# pi_zero_shield.net
KiCad netlist of a schematic drawn in EAGLE
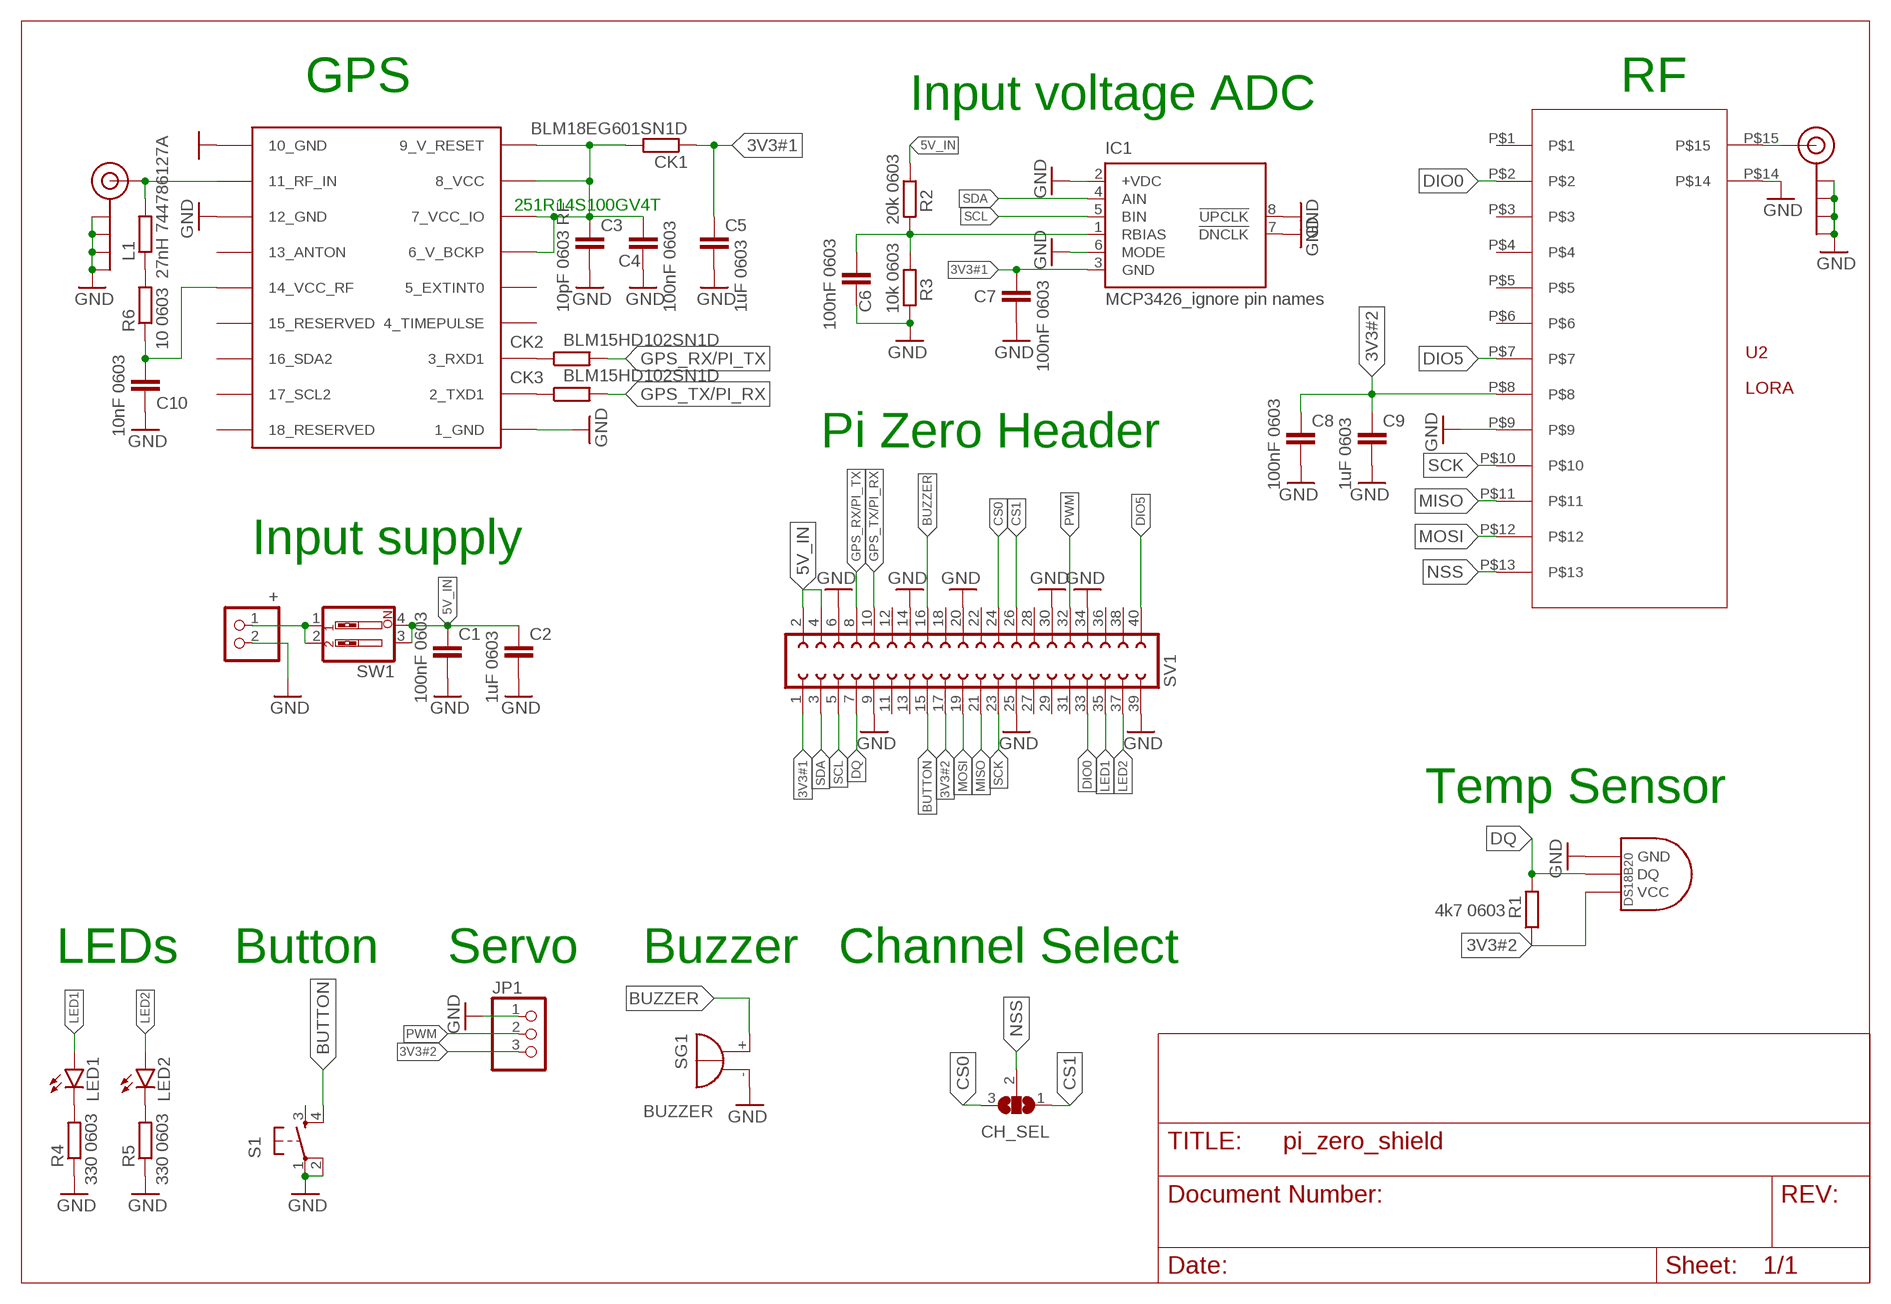
[diagram p0: schematic, sheet 1]

(export (version "E")
  (design (tool "Eeschema 10.0.6"))
  (components
    (comp (ref "+")
      (value "PINHD-1X2")
      (footprint "eagle-import:1X02")
      (libsource (lib "eagle-import") (part "PINHD-1X2"))
    )
    (comp (ref "C1")
      (value "100nF 0603")
      (footprint "eagle-import:C0603K")
      (libsource (lib "eagle-import") (part "C-EUC0603K"))
    )
    (comp (ref "C2")
      (value "1uF 0603")
      (footprint "eagle-import:C0603K")
      (libsource (lib "eagle-import") (part "C-EUC0603K"))
    )
    (comp (ref "C3")
      (value "10pF 0603 RF")
      (footprint "eagle-import:C0603K")
      (libsource (lib "eagle-import") (part "C-EUC0603K"))
    )
    (comp (ref "C4")
      (value "100nF 0603")
      (footprint "eagle-import:C0603K")
      (libsource (lib "eagle-import") (part "C-EUC0603K"))
    )
    (comp (ref "C5")
      (value "1uF 0603")
      (footprint "eagle-import:C0603K")
      (libsource (lib "eagle-import") (part "C-EUC0603K"))
    )
    (comp (ref "C6")
      (value "100nF 0603")
      (footprint "eagle-import:C0603K")
      (libsource (lib "eagle-import") (part "C-EUC0603K"))
    )
    (comp (ref "C7")
      (value "100nF 0603")
      (footprint "eagle-import:C0603K")
      (libsource (lib "eagle-import") (part "C-EUC0603K"))
    )
    (comp (ref "C8")
      (value "100nF 0603")
      (footprint "eagle-import:C0603K")
      (libsource (lib "eagle-import") (part "C-EUC0603K"))
    )
    (comp (ref "C9")
      (value "1uF 0603")
      (footprint "eagle-import:C0603K")
      (libsource (lib "eagle-import") (part "C-EUC0603K"))
    )
    (comp (ref "C10")
      (value "10nF 0603")
      (footprint "eagle-import:C0603K")
      (libsource (lib "eagle-import") (part "C-EUC0603K"))
    )
    (comp (ref "CH_SEL")
      (value "SJ2W")
      (footprint "eagle-import:SJ_2")
      (libsource (lib "eagle-import") (part "SJ2W"))
    )
    (comp (ref "CK1")
      (value "BLM18EG601SN1D")
      (footprint "eagle-import:R0603")
      (libsource (lib "eagle-import") (part "R-EU_R0603"))
    )
    (comp (ref "CK2")
      (value "BLM15HD102SN1D")
      (footprint "eagle-import:R0402")
      (libsource (lib "eagle-import") (part "R-EU_R0402"))
    )
    (comp (ref "CK3")
      (value "BLM15HD102SN1D")
      (footprint "eagle-import:R0402")
      (libsource (lib "eagle-import") (part "R-EU_R0402"))
    )
    (comp (ref "IC1")
      (value "MCP3426_ignore pin names")
      (footprint "eagle-import:SOIC08")
      (libsource (lib "eagle-import") (part "LS7183-SOIC"))
    )
    (comp (ref "J$2")
      (value "SMA_EDGE")
      (footprint "eagle-import:SMA-EDGE")
      (libsource (lib "eagle-import") (part "SMA_EDGE"))
    )
    (comp (ref "JP1")
      (value "PINHD-1X3")
      (footprint "eagle-import:1X03")
      (libsource (lib "eagle-import") (part "PINHD-1X3"))
    )
    (comp (ref "L1")
      (value "27nH 744786127A")
      (footprint "eagle-import:R0603")
      (libsource (lib "eagle-import") (part "R-EU_R0603"))
    )
    (comp (ref "LED1")
      (value "LEDSML0603")
      (footprint "eagle-import:SML0603")
      (libsource (lib "eagle-import") (part "LEDSML0603"))
    )
    (comp (ref "LED2")
      (value "LEDSML0603")
      (footprint "eagle-import:SML0603")
      (libsource (lib "eagle-import") (part "LEDSML0603"))
    )
    (comp (ref "R1")
      (value "4k7 0603")
      (footprint "eagle-import:R0603")
      (libsource (lib "eagle-import") (part "R-EU_R0603"))
    )
    (comp (ref "R2")
      (value "20k 0603")
      (footprint "eagle-import:R0603")
      (libsource (lib "eagle-import") (part "R-EU_R0603"))
    )
    (comp (ref "R3")
      (value "10k 0603")
      (footprint "eagle-import:R0603")
      (libsource (lib "eagle-import") (part "R-EU_R0603"))
    )
    (comp (ref "R4")
      (value "330 0603")
      (footprint "eagle-import:R0603")
      (libsource (lib "eagle-import") (part "R-EU_R0603"))
    )
    (comp (ref "R5")
      (value "330 0603")
      (footprint "eagle-import:R0603")
      (libsource (lib "eagle-import") (part "R-EU_R0603"))
    )
    (comp (ref "R6")
      (value "10 0603")
      (footprint "eagle-import:R0603")
      (libsource (lib "eagle-import") (part "R-EU_R0603"))
    )
    (comp (ref "S1")
      (value "DTS-6")
      (footprint "eagle-import:DTS-6")
      (libsource (lib "eagle-import") (part "DTS-6"))
    )
    (comp (ref "SG1")
      (value "BUZZER")
      (footprint "eagle-import:BMT1205XH7.5")
      (libsource (lib "eagle-import") (part "BMT1205XH7.5"))
    )
    (comp (ref "SV1")
      (value "FE20-2")
      (footprint "eagle-import:FE20-2")
      (libsource (lib "eagle-import") (part "FE20-2"))
    )
    (comp (ref "SW1")
      (value "SW_DIP-2")
      (footprint "eagle-import:EDG-02")
      (libsource (lib "eagle-import") (part "SW_DIP-2"))
    )
    (comp (ref "U$1")
      (value "TAOGLAS.AP.10X.01")
      (footprint "eagle-import:TAOGLAS.AP.10X.01")
      (fields (field (name "SPICEPREFIX") "X"))
      (libsource (lib "eagle-import") (part "TAOGLAS.AP.10X.01"))
    )
    (comp (ref "U$4")
      (value "DS1820SOIC")
      (footprint "eagle-import:DS18B20_SOIC")
      (libsource (lib "eagle-import") (part "DS1820SOIC"))
    )
    (comp (ref "U1")
      (value "U1")
      (footprint "eagle-import:UBLOX_MAX-6")
      (libsource (lib "eagle-import") (part "UBLOX_MAX-6"))
    )
    (comp (ref "U2")
      (value "LORA")
      (footprint "eagle-import:LORA_DRF")
      (libsource (lib "eagle-import") (part "LORA"))
    )
  )
  (nets
    (net (code "1") (name "3V3#1") (class "Default")
      (node (ref "C5") (pin "1") (pinfunction "1_1") (pintype "passive"))
      (node (ref "C7") (pin "1") (pinfunction "1_1") (pintype "passive"))
      (node (ref "CK1") (pin "1") (pinfunction "1_1") (pintype "passive"))
      (node (ref "IC1") (pin "3") (pinfunction "GND_3") (pintype "power_in"))
      (node (ref "SV1") (pin "1") (pinfunction "1_1") (pintype "passive"))
    )
    (net (code "2") (name "3V3#2") (class "Default")
      (node (ref "C8") (pin "1") (pinfunction "1_1") (pintype "passive"))
      (node (ref "C9") (pin "1") (pinfunction "1_1") (pintype "passive"))
      (node (ref "JP1") (pin "3") (pinfunction "3_3") (pintype "passive"))
      (node (ref "R1") (pin "1") (pinfunction "1_1") (pintype "passive"))
      (node (ref "SV1") (pin "17") (pinfunction "17_17") (pintype "passive"))
      (node (ref "U$4") (pin "VCC") (pinfunction "VCC_VCC") (pintype "power_in"))
      (node (ref "U2") (pin "P$8") (pinfunction "P$8_P$8") (pintype "bidirectional"))
    )
    (net (code "3") (name "5V_IN") (class "Default")
      (node (ref "C1") (pin "1") (pinfunction "1_1") (pintype "passive"))
      (node (ref "C2") (pin "1") (pinfunction "1_1") (pintype "passive"))
      (node (ref "R2") (pin "1") (pinfunction "1_1") (pintype "passive"))
      (node (ref "SV1") (pin "2") (pinfunction "2_2") (pintype "passive"))
      (node (ref "SV1") (pin "4") (pinfunction "4_4") (pintype "passive"))
      (node (ref "SW1") (pin "3") (pinfunction "3_3") (pintype "passive"))
      (node (ref "SW1") (pin "4") (pinfunction "4_4") (pintype "passive"))
    )
    (net (code "4") (name "BUTTON") (class "Default")
      (node (ref "S1") (pin "4") (pinfunction "4_4") (pintype "passive"))
      (node (ref "SV1") (pin "15") (pinfunction "15_15") (pintype "passive"))
    )
    (net (code "5") (name "BUZZER") (class "Default")
      (node (ref "SG1") (pin "+") (pinfunction "+_+") (pintype "passive"))
      (node (ref "SV1") (pin "16") (pinfunction "16_16") (pintype "passive"))
    )
    (net (code "6") (name "CS0") (class "Default")
      (node (ref "CH_SEL") (pin "3") (pinfunction "3_3") (pintype "passive"))
      (node (ref "SV1") (pin "24") (pinfunction "24_24") (pintype "passive"))
    )
    (net (code "7") (name "CS1") (class "Default")
      (node (ref "CH_SEL") (pin "1") (pinfunction "1_1") (pintype "passive"))
      (node (ref "SV1") (pin "26") (pinfunction "26_26") (pintype "passive"))
    )
    (net (code "8") (name "DIO0") (class "Default")
      (node (ref "SV1") (pin "33") (pinfunction "33_33") (pintype "passive"))
      (node (ref "U2") (pin "P$2") (pinfunction "P$2_P$2") (pintype "bidirectional"))
    )
    (net (code "9") (name "DIO5") (class "Default")
      (node (ref "SV1") (pin "40") (pinfunction "40_40") (pintype "passive"))
      (node (ref "U2") (pin "P$7") (pinfunction "P$7_P$7") (pintype "bidirectional"))
    )
    (net (code "10") (name "DQ") (class "Default")
      (node (ref "R1") (pin "2") (pinfunction "2_2") (pintype "passive"))
      (node (ref "SV1") (pin "7") (pinfunction "7_7") (pintype "passive"))
      (node (ref "U$4") (pin "DQ") (pinfunction "DQ_DQ") (pintype "bidirectional"))
    )
    (net (code "11") (name "GND") (class "Default")
      (node (ref "+") (pin "2") (pinfunction "2_2") (pintype "passive"))
      (node (ref "C1") (pin "2") (pinfunction "2_2") (pintype "passive"))
      (node (ref "C10") (pin "2") (pinfunction "2_2") (pintype "passive"))
      (node (ref "C2") (pin "2") (pinfunction "2_2") (pintype "passive"))
      (node (ref "C3") (pin "2") (pinfunction "2_2") (pintype "passive"))
      (node (ref "C4") (pin "2") (pinfunction "2_2") (pintype "passive"))
      (node (ref "C5") (pin "2") (pinfunction "2_2") (pintype "passive"))
      (node (ref "C6") (pin "2") (pinfunction "2_2") (pintype "passive"))
      (node (ref "C7") (pin "2") (pinfunction "2_2") (pintype "passive"))
      (node (ref "C8") (pin "2") (pinfunction "2_2") (pintype "passive"))
      (node (ref "C9") (pin "2") (pinfunction "2_2") (pintype "passive"))
      (node (ref "IC1") (pin "2") (pinfunction "+VDC_2") (pintype "input"))
      (node (ref "IC1") (pin "6") (pinfunction "MODE_6") (pintype "input"))
      (node (ref "IC1") (pin "7") (pinfunction "~{DNCLK}_7") (pintype "input"))
      (node (ref "IC1") (pin "8") (pinfunction "~{UPCLK}_8") (pintype "input"))
      (node (ref "J$2") (pin "GND@0") (pinfunction "GND_GND@0") (pintype "bidirectional"))
      (node (ref "J$2") (pin "GND@1") (pinfunction "GND_GND@1") (pintype "bidirectional"))
      (node (ref "J$2") (pin "GND@2") (pinfunction "GND_GND@2") (pintype "bidirectional"))
      (node (ref "J$2") (pin "GND@3") (pinfunction "GND_GND@3") (pintype "bidirectional"))
      (node (ref "JP1") (pin "1") (pinfunction "1_1") (pintype "passive"))
      (node (ref "R3") (pin "2") (pinfunction "2_2") (pintype "passive"))
      (node (ref "R4") (pin "1") (pinfunction "1_1") (pintype "passive"))
      (node (ref "R5") (pin "1") (pinfunction "1_1") (pintype "passive"))
      (node (ref "S1") (pin "1") (pinfunction "1_1") (pintype "passive"))
      (node (ref "S1") (pin "2") (pinfunction "2_2") (pintype "passive"))
      (node (ref "SG1") (pin "-") (pinfunction "-_-") (pintype "passive"))
      (node (ref "SV1") (pin "14") (pinfunction "14_14") (pintype "passive"))
      (node (ref "SV1") (pin "20") (pinfunction "20_20") (pintype "passive"))
      (node (ref "SV1") (pin "25") (pinfunction "25_25") (pintype "passive"))
      (node (ref "SV1") (pin "30") (pinfunction "30_30") (pintype "passive"))
      (node (ref "SV1") (pin "34") (pinfunction "34_34") (pintype "passive"))
      (node (ref "SV1") (pin "39") (pinfunction "39_39") (pintype "passive"))
      (node (ref "SV1") (pin "6") (pinfunction "6_6") (pintype "passive"))
      (node (ref "SV1") (pin "9") (pinfunction "9_9") (pintype "passive"))
      (node (ref "U$1") (pin "GP$1") (pinfunction "GND_GP$1") (pintype "bidirectional"))
      (node (ref "U$1") (pin "GP$2") (pinfunction "GND_GP$2") (pintype "bidirectional"))
      (node (ref "U$1") (pin "GP$3") (pinfunction "GND_GP$3") (pintype "bidirectional"))
      (node (ref "U$1") (pin "GP$4") (pinfunction "GND_GP$4") (pintype "bidirectional"))
      (node (ref "U$4") (pin "GND") (pinfunction "GND_GND") (pintype "power_in"))
      (node (ref "U1") (pin "10_GND") (pinfunction "10_GND_10_GND") (pintype "power_in"))
      (node (ref "U1") (pin "12_GND") (pinfunction "12_GND_12_GND") (pintype "power_in"))
      (node (ref "U1") (pin "1_GND") (pinfunction "1_GND_1_GND") (pintype "power_in"))
      (node (ref "U2") (pin "P$14") (pinfunction "P$14_P$14") (pintype "bidirectional"))
      (node (ref "U2") (pin "P$9") (pinfunction "P$9_P$9") (pintype "bidirectional"))
    )
    (net (code "12") (name "GPS_RX{slash}PI_TX") (class "Default")
      (node (ref "CK2") (pin "2") (pinfunction "2_2") (pintype "passive"))
      (node (ref "SV1") (pin "8") (pinfunction "8_8") (pintype "passive"))
    )
    (net (code "13") (name "GPS_TX{slash}PI_RX") (class "Default")
      (node (ref "CK3") (pin "2") (pinfunction "2_2") (pintype "passive"))
      (node (ref "SV1") (pin "10") (pinfunction "10_10") (pintype "passive"))
    )
    (net (code "14") (name "LED1") (class "Default")
      (node (ref "LED1") (pin "A") (pinfunction "A_A") (pintype "passive"))
      (node (ref "SV1") (pin "35") (pinfunction "35_35") (pintype "passive"))
    )
    (net (code "15") (name "LED2") (class "Default")
      (node (ref "LED2") (pin "A") (pinfunction "A_A") (pintype "passive"))
      (node (ref "SV1") (pin "37") (pinfunction "37_37") (pintype "passive"))
    )
    (net (code "16") (name "MISO") (class "Default")
      (node (ref "SV1") (pin "21") (pinfunction "21_21") (pintype "passive"))
      (node (ref "U2") (pin "P$11") (pinfunction "P$11_P$11") (pintype "bidirectional"))
    )
    (net (code "17") (name "MOSI") (class "Default")
      (node (ref "SV1") (pin "19") (pinfunction "19_19") (pintype "passive"))
      (node (ref "U2") (pin "P$12") (pinfunction "P$12_P$12") (pintype "bidirectional"))
    )
    (net (code "18") (name "NSS") (class "Default")
      (node (ref "CH_SEL") (pin "2") (pinfunction "2_2") (pintype "passive"))
      (node (ref "U2") (pin "P$13") (pinfunction "P$13_P$13") (pintype "bidirectional"))
    )
    (net (code "19") (name "Net-(+-Pad1)") (class "Default")
      (node (ref "+") (pin "1") (pinfunction "1_1") (pintype "passive"))
      (node (ref "SW1") (pin "1") (pinfunction "1_1") (pintype "passive"))
      (node (ref "SW1") (pin "2") (pinfunction "2_2") (pintype "passive"))
    )
    (net (code "20") (name "Net-(C3-Pad1)") (class "Default")
      (node (ref "C3") (pin "1") (pinfunction "1_1") (pintype "passive"))
      (node (ref "C4") (pin "1") (pinfunction "1_1") (pintype "passive"))
      (node (ref "CK1") (pin "2") (pinfunction "2_2") (pintype "passive"))
      (node (ref "U1") (pin "6_V_BCKP") (pinfunction "6_V_BCKP_6_V_BCKP") (pintype "bidirectional"))
      (node (ref "U1") (pin "7_VCC_IO") (pinfunction "7_VCC_IO_7_VCC_IO") (pintype "power_in"))
      (node (ref "U1") (pin "8_VCC") (pinfunction "8_VCC_8_VCC") (pintype "power_in"))
      (node (ref "U1") (pin "9_V_RESET") (pinfunction "9_V_RESET_9_V_RESET") (pintype "power_in"))
    )
    (net (code "21") (name "Net-(C10-Pad1)") (class "Default")
      (node (ref "C10") (pin "1") (pinfunction "1_1") (pintype "passive"))
      (node (ref "R6") (pin "1") (pinfunction "1_1") (pintype "passive"))
      (node (ref "U1") (pin "14_VCC_RF") (pinfunction "14_VCC_RF_14_VCC_RF") (pintype "bidirectional"))
    )
    (net (code "22") (name "Net-(CK2-Pad1)") (class "Default")
      (node (ref "CK2") (pin "1") (pinfunction "1_1") (pintype "passive"))
      (node (ref "U1") (pin "3_RXD1") (pinfunction "3_RXD1_3_RXD1") (pintype "bidirectional"))
    )
    (net (code "23") (name "Net-(CK3-Pad1)") (class "Default")
      (node (ref "CK3") (pin "1") (pinfunction "1_1") (pintype "passive"))
      (node (ref "U1") (pin "2_TXD1") (pinfunction "2_TXD1_2_TXD1") (pintype "bidirectional"))
    )
    (net (code "24") (name "Net-(IC1-RBIAS)") (class "Default")
      (node (ref "C6") (pin "1") (pinfunction "1_1") (pintype "passive"))
      (node (ref "IC1") (pin "1") (pinfunction "RBIAS_1") (pintype "input"))
      (node (ref "R2") (pin "2") (pinfunction "2_2") (pintype "passive"))
      (node (ref "R3") (pin "1") (pinfunction "1_1") (pintype "passive"))
    )
    (net (code "25") (name "Net-(J$2-SIGNAL)") (class "Default")
      (node (ref "J$2") (pin "SIG") (pinfunction "SIGNAL_SIG") (pintype "bidirectional"))
      (node (ref "U2") (pin "P$15") (pinfunction "P$15_P$15") (pintype "bidirectional"))
    )
    (net (code "26") (name "Net-(L1-Pad1)") (class "Default")
      (node (ref "L1") (pin "1") (pinfunction "1_1") (pintype "passive"))
      (node (ref "R6") (pin "2") (pinfunction "2_2") (pintype "passive"))
    )
    (net (code "27") (name "Net-(L1-Pad2)") (class "Default")
      (node (ref "L1") (pin "2") (pinfunction "2_2") (pintype "passive"))
      (node (ref "U$1") (pin "FP$1") (pinfunction "SIGNAL_FP$1") (pintype "bidirectional"))
      (node (ref "U$1") (pin "FP$2") (pinfunction "SIGNAL_FP$2") (pintype "bidirectional"))
      (node (ref "U1") (pin "11_RF_IN") (pinfunction "11_RF_IN_11_RF_IN") (pintype "bidirectional"))
    )
    (net (code "28") (name "Net-(LED1-PadC)") (class "Default")
      (node (ref "LED1") (pin "C") (pinfunction "C_C") (pintype "passive"))
      (node (ref "R4") (pin "2") (pinfunction "2_2") (pintype "passive"))
    )
    (net (code "29") (name "Net-(LED2-PadC)") (class "Default")
      (node (ref "LED2") (pin "C") (pinfunction "C_C") (pintype "passive"))
      (node (ref "R5") (pin "2") (pinfunction "2_2") (pintype "passive"))
    )
    (net (code "30") (name "PWM") (class "Default")
      (node (ref "JP1") (pin "2") (pinfunction "2_2") (pintype "passive"))
      (node (ref "SV1") (pin "32") (pinfunction "32_32") (pintype "passive"))
    )
    (net (code "31") (name "SCK") (class "Default")
      (node (ref "SV1") (pin "23") (pinfunction "23_23") (pintype "passive"))
      (node (ref "U2") (pin "P$10") (pinfunction "P$10_P$10") (pintype "bidirectional"))
    )
    (net (code "32") (name "SCL") (class "Default")
      (node (ref "IC1") (pin "5") (pinfunction "BIN_5") (pintype "input"))
      (node (ref "SV1") (pin "5") (pinfunction "5_5") (pintype "passive"))
    )
    (net (code "33") (name "SDA") (class "Default")
      (node (ref "IC1") (pin "4") (pinfunction "AIN_4") (pintype "input"))
      (node (ref "SV1") (pin "3") (pinfunction "3_3") (pintype "passive"))
    )
    (net (code "34") (name "unconnected-(S1-Pad3)") (class "Default")
      (node (ref "S1") (pin "3") (pinfunction "3_3") (pintype "passive"))
    )
    (net (code "35") (name "unconnected-(SV1-Pad11)") (class "Default")
      (node (ref "SV1") (pin "11") (pinfunction "11_11") (pintype "passive"))
    )
    (net (code "36") (name "unconnected-(SV1-Pad12)") (class "Default")
      (node (ref "SV1") (pin "12") (pinfunction "12_12") (pintype "passive"))
    )
    (net (code "37") (name "unconnected-(SV1-Pad13)") (class "Default")
      (node (ref "SV1") (pin "13") (pinfunction "13_13") (pintype "passive"))
    )
    (net (code "38") (name "unconnected-(SV1-Pad18)") (class "Default")
      (node (ref "SV1") (pin "18") (pinfunction "18_18") (pintype "passive"))
    )
    (net (code "39") (name "unconnected-(SV1-Pad22)") (class "Default")
      (node (ref "SV1") (pin "22") (pinfunction "22_22") (pintype "passive"))
    )
    (net (code "40") (name "unconnected-(SV1-Pad27)") (class "Default")
      (node (ref "SV1") (pin "27") (pinfunction "27_27") (pintype "passive"))
    )
    (net (code "41") (name "unconnected-(SV1-Pad28)") (class "Default")
      (node (ref "SV1") (pin "28") (pinfunction "28_28") (pintype "passive"))
    )
    (net (code "42") (name "unconnected-(SV1-Pad29)") (class "Default")
      (node (ref "SV1") (pin "29") (pinfunction "29_29") (pintype "passive"))
    )
    (net (code "43") (name "unconnected-(SV1-Pad31)") (class "Default")
      (node (ref "SV1") (pin "31") (pinfunction "31_31") (pintype "passive"))
    )
    (net (code "44") (name "unconnected-(SV1-Pad36)") (class "Default")
      (node (ref "SV1") (pin "36") (pinfunction "36_36") (pintype "passive"))
    )
    (net (code "45") (name "unconnected-(SV1-Pad38)") (class "Default")
      (node (ref "SV1") (pin "38") (pinfunction "38_38") (pintype "passive"))
    )
    (net (code "46") (name "unconnected-(U1-Pad4_TIMEPULSE)") (class "Default")
      (node (ref "U1") (pin "4_TIMEPULSE") (pinfunction "4_TIMEPULSE_4_TIMEPULSE") (pintype "bidirectional"))
    )
    (net (code "47") (name "unconnected-(U1-Pad5_EXTINT0)") (class "Default")
      (node (ref "U1") (pin "5_EXTINT0") (pinfunction "5_EXTINT0_5_EXTINT0") (pintype "bidirectional"))
    )
    (net (code "48") (name "unconnected-(U1-Pad13_ANTON)") (class "Default")
      (node (ref "U1") (pin "13_ANTON") (pinfunction "13_ANTON_13_ANTON") (pintype "bidirectional"))
    )
    (net (code "49") (name "unconnected-(U1-Pad15_RESERVED)") (class "Default")
      (node (ref "U1") (pin "15_RESERVED") (pinfunction "15_RESERVED_15_RESERVED") (pintype "bidirectional"))
    )
    (net (code "50") (name "unconnected-(U1-Pad16_SDA2)") (class "Default")
      (node (ref "U1") (pin "16_SDA2") (pinfunction "16_SDA2_16_SDA2") (pintype "bidirectional"))
    )
    (net (code "51") (name "unconnected-(U1-Pad17_SCL2)") (class "Default")
      (node (ref "U1") (pin "17_SCL2") (pinfunction "17_SCL2_17_SCL2") (pintype "bidirectional"))
    )
    (net (code "52") (name "unconnected-(U1-Pad18_RESERVED)") (class "Default")
      (node (ref "U1") (pin "18_RESERVED") (pinfunction "18_RESERVED_18_RESERVED") (pintype "bidirectional"))
    )
    (net (code "53") (name "unconnected-(U2-PadP$1)") (class "Default")
      (node (ref "U2") (pin "P$1") (pinfunction "P$1_P$1") (pintype "bidirectional"))
    )
    (net (code "54") (name "unconnected-(U2-PadP$3)") (class "Default")
      (node (ref "U2") (pin "P$3") (pinfunction "P$3_P$3") (pintype "bidirectional"))
    )
    (net (code "55") (name "unconnected-(U2-PadP$4)") (class "Default")
      (node (ref "U2") (pin "P$4") (pinfunction "P$4_P$4") (pintype "bidirectional"))
    )
    (net (code "56") (name "unconnected-(U2-PadP$5)") (class "Default")
      (node (ref "U2") (pin "P$5") (pinfunction "P$5_P$5") (pintype "bidirectional"))
    )
    (net (code "57") (name "unconnected-(U2-PadP$6)") (class "Default")
      (node (ref "U2") (pin "P$6") (pinfunction "P$6_P$6") (pintype "bidirectional"))
    )
  )
)
